# Solid_State_Timer_v1_0.net
KiCad netlist of a schematic drawn in EAGLE
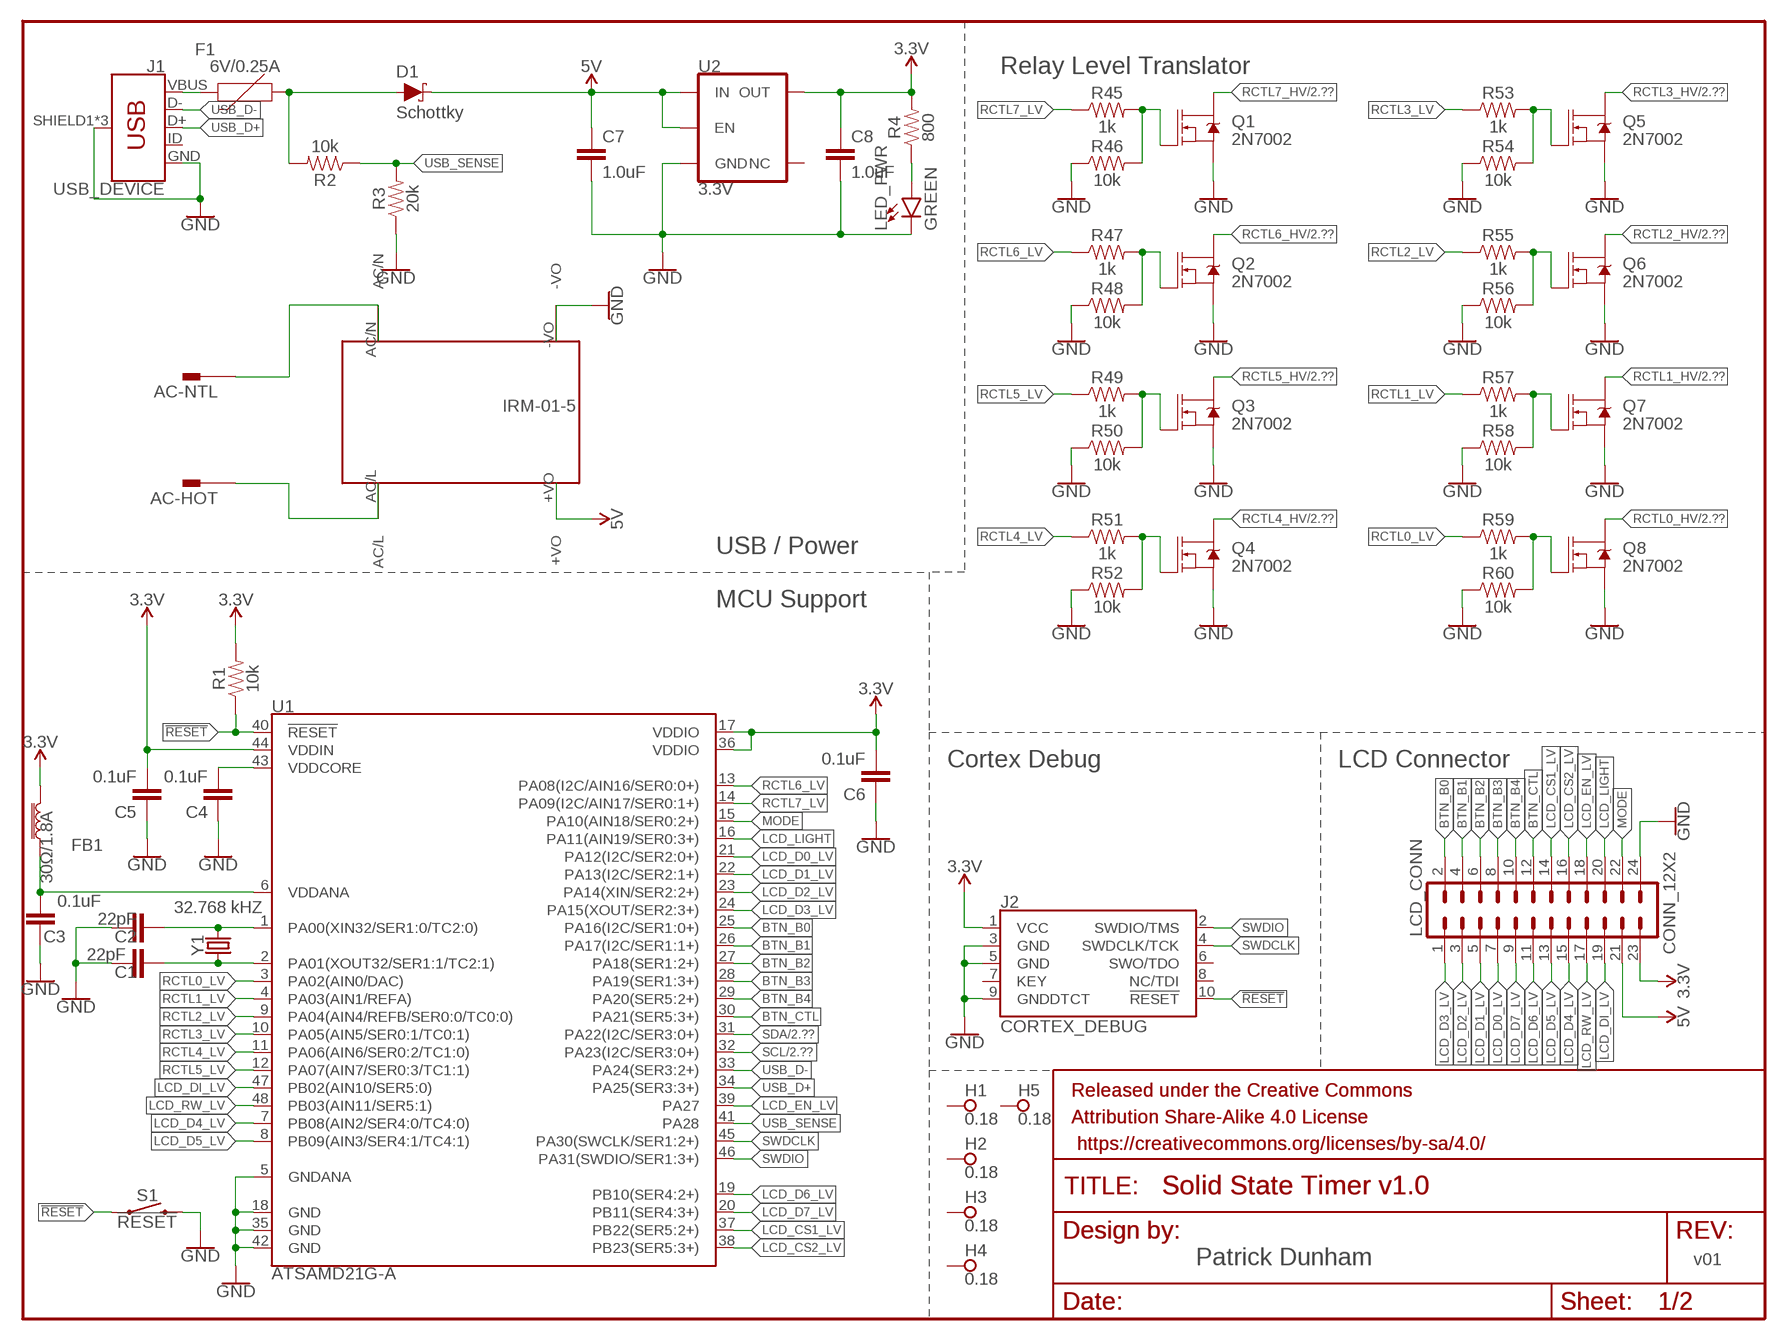
[diagram p0: schematic, sheet 1]
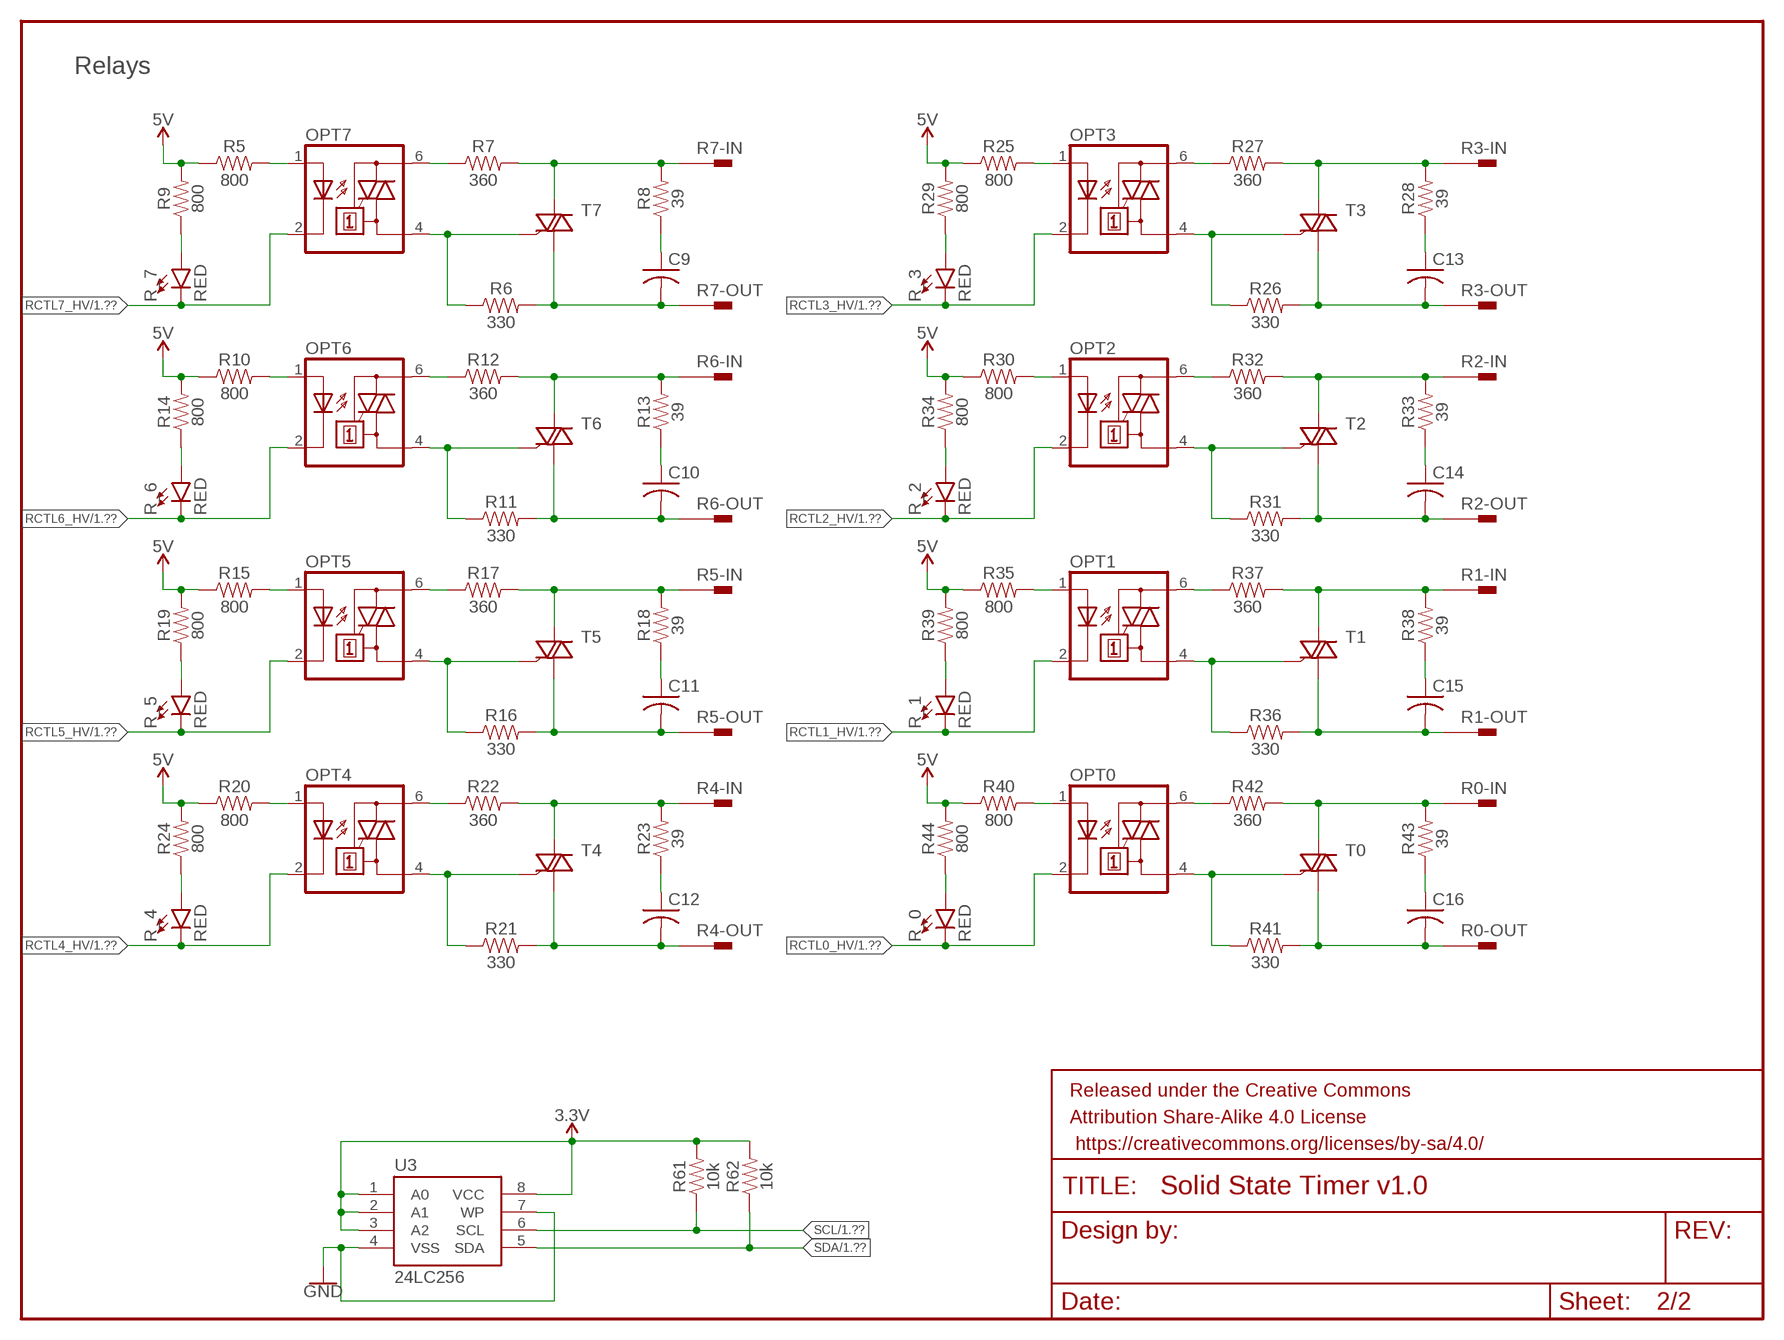
[diagram p1: schematic, sheet 2]

(export (version "E")
  (design (tool "Eeschema 10.0.6"))
  (components
    (comp (ref "C9")
      (value "C-USC1206")
      (footprint "eagle-import:C1206")
      (libsource (lib "eagle-import") (part "C-USC1206"))
    )
    (comp (ref "C10")
      (value "C-USC1206")
      (footprint "eagle-import:C1206")
      (libsource (lib "eagle-import") (part "C-USC1206"))
    )
    (comp (ref "C11")
      (value "C-USC1206")
      (footprint "eagle-import:C1206")
      (libsource (lib "eagle-import") (part "C-USC1206"))
    )
    (comp (ref "C12")
      (value "C-USC1206")
      (footprint "eagle-import:C1206")
      (libsource (lib "eagle-import") (part "C-USC1206"))
    )
    (comp (ref "C13")
      (value "C-USC1206")
      (footprint "eagle-import:C1206")
      (libsource (lib "eagle-import") (part "C-USC1206"))
    )
    (comp (ref "C14")
      (value "C-USC1206")
      (footprint "eagle-import:C1206")
      (libsource (lib "eagle-import") (part "C-USC1206"))
    )
    (comp (ref "C15")
      (value "C-USC1206")
      (footprint "eagle-import:C1206")
      (libsource (lib "eagle-import") (part "C-USC1206"))
    )
    (comp (ref "C16")
      (value "C-USC1206")
      (footprint "eagle-import:C1206")
      (libsource (lib "eagle-import") (part "C-USC1206"))
    )
    (comp (ref "FRAME2")
      (value "FRAME-LETTERNO_PACKAGE")
      (footprint "eagle-import:DUMMY")
      (fields (field (name "DESIGNER") "Nobody"))
      (libsource (lib "eagle-import") (part "FRAME-LETTERNO_PACKAGE"))
    )
    (comp (ref "OPT0")
      (value "MOC3031M")
      (footprint "eagle-import:DIL06")
      (fields (field (name "MF") "FAIRCHILD SEMICONDUCTOR"))
      (libsource (lib "eagle-import") (part "MOC3031M"))
    )
    (comp (ref "OPT1")
      (value "MOC3031M")
      (footprint "eagle-import:DIL06")
      (fields (field (name "MF") "FAIRCHILD SEMICONDUCTOR"))
      (libsource (lib "eagle-import") (part "MOC3031M"))
    )
    (comp (ref "OPT2")
      (value "MOC3031M")
      (footprint "eagle-import:DIL06")
      (fields (field (name "MF") "FAIRCHILD SEMICONDUCTOR"))
      (libsource (lib "eagle-import") (part "MOC3031M"))
    )
    (comp (ref "OPT3")
      (value "MOC3031M")
      (footprint "eagle-import:DIL06")
      (fields (field (name "MF") "FAIRCHILD SEMICONDUCTOR"))
      (libsource (lib "eagle-import") (part "MOC3031M"))
    )
    (comp (ref "OPT4")
      (value "MOC3031M")
      (footprint "eagle-import:DIL06")
      (fields (field (name "MF") "FAIRCHILD SEMICONDUCTOR"))
      (libsource (lib "eagle-import") (part "MOC3031M"))
    )
    (comp (ref "OPT5")
      (value "MOC3031M")
      (footprint "eagle-import:DIL06")
      (fields (field (name "MF") "FAIRCHILD SEMICONDUCTOR"))
      (libsource (lib "eagle-import") (part "MOC3031M"))
    )
    (comp (ref "OPT6")
      (value "MOC3031M")
      (footprint "eagle-import:DIL06")
      (fields (field (name "MF") "FAIRCHILD SEMICONDUCTOR"))
      (libsource (lib "eagle-import") (part "MOC3031M"))
    )
    (comp (ref "OPT7")
      (value "MOC3031M")
      (footprint "eagle-import:DIL06")
      (fields (field (name "MF") "FAIRCHILD SEMICONDUCTOR"))
      (libsource (lib "eagle-import") (part "MOC3031M"))
    )
    (comp (ref "R0-IN")
      (value "PIN262409-1")
      (footprint "eagle-import:62409-1")
      (libsource (lib "eagle-import") (part "PIN262409-1"))
    )
    (comp (ref "R0-OUT")
      (value "PIN262409-1")
      (footprint "eagle-import:62409-1")
      (libsource (lib "eagle-import") (part "PIN262409-1"))
    )
    (comp (ref "R1-IN")
      (value "PIN262409-1")
      (footprint "eagle-import:62409-1")
      (libsource (lib "eagle-import") (part "PIN262409-1"))
    )
    (comp (ref "R1-OUT")
      (value "PIN262409-1")
      (footprint "eagle-import:62409-1")
      (libsource (lib "eagle-import") (part "PIN262409-1"))
    )
    (comp (ref "R2-IN")
      (value "PIN262409-1")
      (footprint "eagle-import:62409-1")
      (libsource (lib "eagle-import") (part "PIN262409-1"))
    )
    (comp (ref "R2-OUT")
      (value "PIN262409-1")
      (footprint "eagle-import:62409-1")
      (libsource (lib "eagle-import") (part "PIN262409-1"))
    )
    (comp (ref "R3-IN")
      (value "PIN262409-1")
      (footprint "eagle-import:62409-1")
      (libsource (lib "eagle-import") (part "PIN262409-1"))
    )
    (comp (ref "R3-OUT")
      (value "PIN262409-1")
      (footprint "eagle-import:62409-1")
      (libsource (lib "eagle-import") (part "PIN262409-1"))
    )
    (comp (ref "R4-IN")
      (value "PIN262409-1")
      (footprint "eagle-import:62409-1")
      (libsource (lib "eagle-import") (part "PIN262409-1"))
    )
    (comp (ref "R4-OUT")
      (value "PIN262409-1")
      (footprint "eagle-import:62409-1")
      (libsource (lib "eagle-import") (part "PIN262409-1"))
    )
    (comp (ref "R5")
      (value "800")
      (footprint "eagle-import:0603")
      (libsource (lib "eagle-import") (part "180OHM-0603-1/10W-1%"))
    )
    (comp (ref "R5-IN")
      (value "PIN262409-1")
      (footprint "eagle-import:62409-1")
      (libsource (lib "eagle-import") (part "PIN262409-1"))
    )
    (comp (ref "R5-OUT")
      (value "PIN262409-1")
      (footprint "eagle-import:62409-1")
      (libsource (lib "eagle-import") (part "PIN262409-1"))
    )
    (comp (ref "R6")
      (value "330")
      (footprint "eagle-import:0603")
      (libsource (lib "eagle-import") (part "330OHM-0603-1/10W-1%"))
    )
    (comp (ref "R6-IN")
      (value "PIN262409-1")
      (footprint "eagle-import:62409-1")
      (libsource (lib "eagle-import") (part "PIN262409-1"))
    )
    (comp (ref "R6-OUT")
      (value "PIN262409-1")
      (footprint "eagle-import:62409-1")
      (libsource (lib "eagle-import") (part "PIN262409-1"))
    )
    (comp (ref "R7")
      (value "360")
      (footprint "eagle-import:0603")
      (libsource (lib "eagle-import") (part "390OHM-0603-1/10W-1%"))
    )
    (comp (ref "R7-IN")
      (value "PIN262409-1")
      (footprint "eagle-import:62409-1")
      (libsource (lib "eagle-import") (part "PIN262409-1"))
    )
    (comp (ref "R7-OUT")
      (value "PIN262409-1")
      (footprint "eagle-import:62409-1")
      (libsource (lib "eagle-import") (part "PIN262409-1"))
    )
    (comp (ref "R8")
      (value "39")
      (footprint "eagle-import:0603")
      (libsource (lib "eagle-import") (part "39KOHM-0603-1/10W-1%"))
    )
    (comp (ref "R9")
      (value "800")
      (footprint "eagle-import:0603")
      (libsource (lib "eagle-import") (part "680OHM-0603-1/10W-5%"))
    )
    (comp (ref "R10")
      (value "800")
      (footprint "eagle-import:0603")
      (libsource (lib "eagle-import") (part "180OHM-0603-1/10W-1%"))
    )
    (comp (ref "R11")
      (value "330")
      (footprint "eagle-import:0603")
      (libsource (lib "eagle-import") (part "330OHM-0603-1/10W-1%"))
    )
    (comp (ref "R12")
      (value "360")
      (footprint "eagle-import:0603")
      (libsource (lib "eagle-import") (part "390OHM-0603-1/10W-1%"))
    )
    (comp (ref "R13")
      (value "39")
      (footprint "eagle-import:0603")
      (libsource (lib "eagle-import") (part "39KOHM-0603-1/10W-1%"))
    )
    (comp (ref "R14")
      (value "800")
      (footprint "eagle-import:0603")
      (libsource (lib "eagle-import") (part "680OHM-0603-1/10W-5%"))
    )
    (comp (ref "R15")
      (value "800")
      (footprint "eagle-import:0603")
      (libsource (lib "eagle-import") (part "180OHM-0603-1/10W-1%"))
    )
    (comp (ref "R16")
      (value "330")
      (footprint "eagle-import:0603")
      (libsource (lib "eagle-import") (part "330OHM-0603-1/10W-1%"))
    )
    (comp (ref "R17")
      (value "360")
      (footprint "eagle-import:0603")
      (libsource (lib "eagle-import") (part "390OHM-0603-1/10W-1%"))
    )
    (comp (ref "R18")
      (value "39")
      (footprint "eagle-import:0603")
      (libsource (lib "eagle-import") (part "39KOHM-0603-1/10W-1%"))
    )
    (comp (ref "R19")
      (value "800")
      (footprint "eagle-import:0603")
      (libsource (lib "eagle-import") (part "680OHM-0603-1/10W-5%"))
    )
    (comp (ref "R20")
      (value "800")
      (footprint "eagle-import:0603")
      (libsource (lib "eagle-import") (part "180OHM-0603-1/10W-1%"))
    )
    (comp (ref "R21")
      (value "330")
      (footprint "eagle-import:0603")
      (libsource (lib "eagle-import") (part "330OHM-0603-1/10W-1%"))
    )
    (comp (ref "R22")
      (value "360")
      (footprint "eagle-import:0603")
      (libsource (lib "eagle-import") (part "390OHM-0603-1/10W-1%"))
    )
    (comp (ref "R23")
      (value "39")
      (footprint "eagle-import:0603")
      (libsource (lib "eagle-import") (part "39KOHM-0603-1/10W-1%"))
    )
    (comp (ref "R24")
      (value "800")
      (footprint "eagle-import:0603")
      (libsource (lib "eagle-import") (part "680OHM-0603-1/10W-5%"))
    )
    (comp (ref "R25")
      (value "800")
      (footprint "eagle-import:0603")
      (libsource (lib "eagle-import") (part "180OHM-0603-1/10W-1%"))
    )
    (comp (ref "R26")
      (value "330")
      (footprint "eagle-import:0603")
      (libsource (lib "eagle-import") (part "330OHM-0603-1/10W-1%"))
    )
    (comp (ref "R27")
      (value "360")
      (footprint "eagle-import:0603")
      (libsource (lib "eagle-import") (part "390OHM-0603-1/10W-1%"))
    )
    (comp (ref "R28")
      (value "39")
      (footprint "eagle-import:0603")
      (libsource (lib "eagle-import") (part "39KOHM-0603-1/10W-1%"))
    )
    (comp (ref "R29")
      (value "800")
      (footprint "eagle-import:0603")
      (libsource (lib "eagle-import") (part "680OHM-0603-1/10W-5%"))
    )
    (comp (ref "R30")
      (value "800")
      (footprint "eagle-import:0603")
      (libsource (lib "eagle-import") (part "180OHM-0603-1/10W-1%"))
    )
    (comp (ref "R31")
      (value "330")
      (footprint "eagle-import:0603")
      (libsource (lib "eagle-import") (part "330OHM-0603-1/10W-1%"))
    )
    (comp (ref "R32")
      (value "360")
      (footprint "eagle-import:0603")
      (libsource (lib "eagle-import") (part "390OHM-0603-1/10W-1%"))
    )
    (comp (ref "R33")
      (value "39")
      (footprint "eagle-import:0603")
      (libsource (lib "eagle-import") (part "39KOHM-0603-1/10W-1%"))
    )
    (comp (ref "R34")
      (value "800")
      (footprint "eagle-import:0603")
      (libsource (lib "eagle-import") (part "680OHM-0603-1/10W-5%"))
    )
    (comp (ref "R35")
      (value "800")
      (footprint "eagle-import:0603")
      (libsource (lib "eagle-import") (part "180OHM-0603-1/10W-1%"))
    )
    (comp (ref "R36")
      (value "330")
      (footprint "eagle-import:0603")
      (libsource (lib "eagle-import") (part "330OHM-0603-1/10W-1%"))
    )
    (comp (ref "R37")
      (value "360")
      (footprint "eagle-import:0603")
      (libsource (lib "eagle-import") (part "390OHM-0603-1/10W-1%"))
    )
    (comp (ref "R38")
      (value "39")
      (footprint "eagle-import:0603")
      (libsource (lib "eagle-import") (part "39KOHM-0603-1/10W-1%"))
    )
    (comp (ref "R39")
      (value "800")
      (footprint "eagle-import:0603")
      (libsource (lib "eagle-import") (part "680OHM-0603-1/10W-5%"))
    )
    (comp (ref "R40")
      (value "800")
      (footprint "eagle-import:0603")
      (libsource (lib "eagle-import") (part "180OHM-0603-1/10W-1%"))
    )
    (comp (ref "R41")
      (value "330")
      (footprint "eagle-import:0603")
      (libsource (lib "eagle-import") (part "330OHM-0603-1/10W-1%"))
    )
    (comp (ref "R42")
      (value "360")
      (footprint "eagle-import:0603")
      (libsource (lib "eagle-import") (part "390OHM-0603-1/10W-1%"))
    )
    (comp (ref "R43")
      (value "39")
      (footprint "eagle-import:0603")
      (libsource (lib "eagle-import") (part "39KOHM-0603-1/10W-1%"))
    )
    (comp (ref "R44")
      (value "800")
      (footprint "eagle-import:0603")
      (libsource (lib "eagle-import") (part "680OHM-0603-1/10W-5%"))
    )
    (comp (ref "R61")
      (value "10k")
      (footprint "eagle-import:0603")
      (libsource (lib "eagle-import") (part "10KOHM-0603-1/10W-1%"))
    )
    (comp (ref "R62")
      (value "10k")
      (footprint "eagle-import:0603")
      (libsource (lib "eagle-import") (part "10KOHM-0603-1/10W-1%"))
    )
    (comp (ref "R_0")
      (value "RED")
      (footprint "eagle-import:LED-0603")
      (libsource (lib "eagle-import") (part "LED-RED0603"))
    )
    (comp (ref "R_1")
      (value "RED")
      (footprint "eagle-import:LED-0603")
      (libsource (lib "eagle-import") (part "LED-RED0603"))
    )
    (comp (ref "R_2")
      (value "RED")
      (footprint "eagle-import:LED-0603")
      (libsource (lib "eagle-import") (part "LED-RED0603"))
    )
    (comp (ref "R_3")
      (value "RED")
      (footprint "eagle-import:LED-0603")
      (libsource (lib "eagle-import") (part "LED-RED0603"))
    )
    (comp (ref "R_4")
      (value "RED")
      (footprint "eagle-import:LED-0603")
      (libsource (lib "eagle-import") (part "LED-RED0603"))
    )
    (comp (ref "R_5")
      (value "RED")
      (footprint "eagle-import:LED-0603")
      (libsource (lib "eagle-import") (part "LED-RED0603"))
    )
    (comp (ref "R_6")
      (value "RED")
      (footprint "eagle-import:LED-0603")
      (libsource (lib "eagle-import") (part "LED-RED0603"))
    )
    (comp (ref "R_7")
      (value "RED")
      (footprint "eagle-import:LED-0603")
      (libsource (lib "eagle-import") (part "LED-RED0603"))
    )
    (comp (ref "T0")
      (value "BT138-V")
      (footprint "eagle-import:TO220BV")
      (libsource (lib "eagle-import") (part "BT138-V"))
    )
    (comp (ref "T1")
      (value "BT138-V")
      (footprint "eagle-import:TO220BV")
      (libsource (lib "eagle-import") (part "BT138-V"))
    )
    (comp (ref "T2")
      (value "BT138-V")
      (footprint "eagle-import:TO220BV")
      (libsource (lib "eagle-import") (part "BT138-V"))
    )
    (comp (ref "T3")
      (value "BT138-V")
      (footprint "eagle-import:TO220BV")
      (libsource (lib "eagle-import") (part "BT138-V"))
    )
    (comp (ref "T4")
      (value "BT138-V")
      (footprint "eagle-import:TO220BV")
      (libsource (lib "eagle-import") (part "BT138-V"))
    )
    (comp (ref "T5")
      (value "BT138-V")
      (footprint "eagle-import:TO220BV")
      (libsource (lib "eagle-import") (part "BT138-V"))
    )
    (comp (ref "T6")
      (value "BT138-V")
      (footprint "eagle-import:TO220BV")
      (libsource (lib "eagle-import") (part "BT138-V"))
    )
    (comp (ref "T7")
      (value "BT138-V")
      (footprint "eagle-import:TO220BV")
      (libsource (lib "eagle-import") (part "BT138-V"))
    )
    (comp (ref "U3")
      (value "24LC256")
      (footprint "eagle-import:SO08")
      (libsource (lib "eagle-import") (part "EEPROM-I2CSMD"))
    )
    (comp (ref "AC-HOT")
      (value "PIN262409-1")
      (footprint "eagle-import:62409-1")
      (libsource (lib "eagle-import") (part "PIN262409-1"))
    )
    (comp (ref "AC-NTL")
      (value "PIN262409-1")
      (footprint "eagle-import:62409-1")
      (libsource (lib "eagle-import") (part "PIN262409-1"))
    )
    (comp (ref "C1")
      (value "22pF")
      (footprint "eagle-import:0603")
      (libsource (lib "eagle-import") (part "22PF-0603-50V-5%"))
    )
    (comp (ref "C2")
      (value "22pF")
      (footprint "eagle-import:0603")
      (libsource (lib "eagle-import") (part "22PF-0603-50V-5%"))
    )
    (comp (ref "C3")
      (value "0.1uF")
      (footprint "eagle-import:0603")
      (libsource (lib "eagle-import") (part "0.1UF-0603-25V-5%"))
    )
    (comp (ref "C4")
      (value "0.1uF")
      (footprint "eagle-import:0603")
      (libsource (lib "eagle-import") (part "0.1UF-0603-25V-5%"))
    )
    (comp (ref "C5")
      (value "0.1uF")
      (footprint "eagle-import:0603")
      (libsource (lib "eagle-import") (part "0.1UF-0603-25V-5%"))
    )
    (comp (ref "C6")
      (value "0.1uF")
      (footprint "eagle-import:0603")
      (libsource (lib "eagle-import") (part "0.1UF-0603-25V-5%"))
    )
    (comp (ref "C7")
      (value "1.0uF")
      (footprint "eagle-import:0603")
      (libsource (lib "eagle-import") (part "1.0UF-0603-16V-10%"))
    )
    (comp (ref "C8")
      (value "1.0uF")
      (footprint "eagle-import:0603")
      (libsource (lib "eagle-import") (part "1.0UF-0603-16V-10%"))
    )
    (comp (ref "D1")
      (value "Schottky")
      (footprint "eagle-import:SOT23-3")
      (libsource (lib "eagle-import") (part "DIODE-SCHOTTKY-ZLLS500"))
    )
    (comp (ref "F1")
      (value "6V/0.25A")
      (footprint "eagle-import:1206")
      (libsource (lib "eagle-import") (part "PPTC_THREE-QUARTER-AMP"))
    )
    (comp (ref "FB1")
      (value "30Ω/1.8A")
      (footprint "eagle-import:0603")
      (libsource (lib "eagle-import") (part "FERRITE_BEAD-0603"))
    )
    (comp (ref "FRAME1")
      (value "FRAME-LETTERNO_PACKAGE")
      (footprint "eagle-import:DUMMY")
      (fields (field (name "DESIGNER") "Nobody"))
      (libsource (lib "eagle-import") (part "FRAME-LETTERNO_PACKAGE"))
    )
    (comp (ref "FRAME3")
      (value "FRAME-LETTERNO_PACKAGE")
      (footprint "eagle-import:DUMMY")
      (fields
        (field (name "DESIGNER") "Nobody")
        (field (name "VERSION") "v01")
        (field (name "DESIGNER_1") "Patrick Dunham")
      )
      (libsource (lib "eagle-import") (part "FRAME-LETTERNO_PACKAGE"))
    )
    (comp (ref "H1")
      (value "0.18")
      (footprint "eagle-import:PAD_0.1800")
      (libsource (lib "eagle-import") (part "SPECIAL_DRILL_0.1800"))
    )
    (comp (ref "H2")
      (value "0.18")
      (footprint "eagle-import:PAD_0.1800")
      (libsource (lib "eagle-import") (part "SPECIAL_DRILL_0.1800"))
    )
    (comp (ref "H3")
      (value "0.18")
      (footprint "eagle-import:PAD_0.1800")
      (libsource (lib "eagle-import") (part "SPECIAL_DRILL_0.1800"))
    )
    (comp (ref "H4")
      (value "0.18")
      (footprint "eagle-import:PAD_0.1800")
      (libsource (lib "eagle-import") (part "SPECIAL_DRILL_0.1800"))
    )
    (comp (ref "H5")
      (value "0.18")
      (footprint "eagle-import:PAD_0.1800")
      (libsource (lib "eagle-import") (part "SPECIAL_DRILL_0.1800"))
    )
    (comp (ref "J1")
      (value "USB_DEVICE")
      (footprint "eagle-import:USB-B-MICRO-SMD")
      (libsource (lib "eagle-import") (part "USB_MICRO-B_FEMALE-SMT"))
    )
    (comp (ref "J2")
      (value "CORTEX_DEBUG")
      (footprint "eagle-import:2X5-PTH-1.27MM")
      (libsource (lib "eagle-import") (part "CORTEX_DEBUG_PTH"))
    )
    (comp (ref "LCD_CONN")
      (value "CONN_12X2")
      (footprint "eagle-import:2X12")
      (libsource (lib "eagle-import") (part "CONN_12X2"))
    )
    (comp (ref "LED_PWR")
      (value "GREEN")
      (footprint "eagle-import:LED-0603")
      (libsource (lib "eagle-import") (part "LED0603"))
    )
    (comp (ref "Q1")
      (value "2N7002")
      (footprint "eagle-import:SOT323")
      (libsource (lib "eagle-import") (part "MOSFET-NCH-2N7002PW"))
    )
    (comp (ref "Q2")
      (value "2N7002")
      (footprint "eagle-import:SOT323")
      (libsource (lib "eagle-import") (part "MOSFET-NCH-2N7002PW"))
    )
    (comp (ref "Q3")
      (value "2N7002")
      (footprint "eagle-import:SOT323")
      (libsource (lib "eagle-import") (part "MOSFET-NCH-2N7002PW"))
    )
    (comp (ref "Q4")
      (value "2N7002")
      (footprint "eagle-import:SOT323")
      (libsource (lib "eagle-import") (part "MOSFET-NCH-2N7002PW"))
    )
    (comp (ref "Q5")
      (value "2N7002")
      (footprint "eagle-import:SOT323")
      (libsource (lib "eagle-import") (part "MOSFET-NCH-2N7002PW"))
    )
    (comp (ref "Q6")
      (value "2N7002")
      (footprint "eagle-import:SOT323")
      (libsource (lib "eagle-import") (part "MOSFET-NCH-2N7002PW"))
    )
    (comp (ref "Q7")
      (value "2N7002")
      (footprint "eagle-import:SOT323")
      (libsource (lib "eagle-import") (part "MOSFET-NCH-2N7002PW"))
    )
    (comp (ref "Q8")
      (value "2N7002")
      (footprint "eagle-import:SOT323")
      (libsource (lib "eagle-import") (part "MOSFET-NCH-2N7002PW"))
    )
    (comp (ref "R1")
      (value "10k")
      (footprint "eagle-import:0603")
      (libsource (lib "eagle-import") (part "10KOHM-0603-1/10W-1%"))
    )
    (comp (ref "R2")
      (value "10k")
      (footprint "eagle-import:0603")
      (libsource (lib "eagle-import") (part "10KOHM-0603-1/10W-1%"))
    )
    (comp (ref "R3")
      (value "20k")
      (footprint "eagle-import:0603")
      (libsource (lib "eagle-import") (part "20KOHM-0603-1/10W-5%"))
    )
    (comp (ref "R4")
      (value "800")
      (footprint "eagle-import:0603")
      (libsource (lib "eagle-import") (part "330OHM-0603-1/10W-1%"))
    )
    (comp (ref "R45")
      (value "1k")
      (footprint "eagle-import:0603")
      (libsource (lib "eagle-import") (part "1KOHM-0603-1/10W-1%"))
    )
    (comp (ref "R46")
      (value "10k")
      (footprint "eagle-import:0603")
      (libsource (lib "eagle-import") (part "10KOHM-0603-1/10W-1%"))
    )
    (comp (ref "R47")
      (value "1k")
      (footprint "eagle-import:0603")
      (libsource (lib "eagle-import") (part "1KOHM-0603-1/10W-1%"))
    )
    (comp (ref "R48")
      (value "10k")
      (footprint "eagle-import:0603")
      (libsource (lib "eagle-import") (part "10KOHM-0603-1/10W-1%"))
    )
    (comp (ref "R49")
      (value "1k")
      (footprint "eagle-import:0603")
      (libsource (lib "eagle-import") (part "1KOHM-0603-1/10W-1%"))
    )
    (comp (ref "R50")
      (value "10k")
      (footprint "eagle-import:0603")
      (libsource (lib "eagle-import") (part "10KOHM-0603-1/10W-1%"))
    )
    (comp (ref "R51")
      (value "1k")
      (footprint "eagle-import:0603")
      (libsource (lib "eagle-import") (part "1KOHM-0603-1/10W-1%"))
    )
    (comp (ref "R52")
      (value "10k")
      (footprint "eagle-import:0603")
      (libsource (lib "eagle-import") (part "10KOHM-0603-1/10W-1%"))
    )
    (comp (ref "R53")
      (value "1k")
      (footprint "eagle-import:0603")
      (libsource (lib "eagle-import") (part "1KOHM-0603-1/10W-1%"))
    )
    (comp (ref "R54")
      (value "10k")
      (footprint "eagle-import:0603")
      (libsource (lib "eagle-import") (part "10KOHM-0603-1/10W-1%"))
    )
    (comp (ref "R55")
      (value "1k")
      (footprint "eagle-import:0603")
      (libsource (lib "eagle-import") (part "1KOHM-0603-1/10W-1%"))
    )
    (comp (ref "R56")
      (value "10k")
      (footprint "eagle-import:0603")
      (libsource (lib "eagle-import") (part "10KOHM-0603-1/10W-1%"))
    )
    (comp (ref "R57")
      (value "1k")
      (footprint "eagle-import:0603")
      (libsource (lib "eagle-import") (part "1KOHM-0603-1/10W-1%"))
    )
    (comp (ref "R58")
      (value "10k")
      (footprint "eagle-import:0603")
      (libsource (lib "eagle-import") (part "10KOHM-0603-1/10W-1%"))
    )
    (comp (ref "R59")
      (value "1k")
      (footprint "eagle-import:0603")
      (libsource (lib "eagle-import") (part "1KOHM-0603-1/10W-1%"))
    )
    (comp (ref "R60")
      (value "10k")
      (footprint "eagle-import:0603")
      (libsource (lib "eagle-import") (part "10KOHM-0603-1/10W-1%"))
    )
    (comp (ref "S1")
      (value "!RESET")
      (footprint "eagle-import:TACTILE_SWITCH_PTH_RIGHT_ANGLE_KIT")
      (libsource (lib "eagle-import") (part "MOMENTARY-SWITCH-SPST-PTH-RIGHT-ANGLE-KIT"))
    )
    (comp (ref "U$1")
      (value "IRM-05-1")
      (footprint "eagle-import:IRM-01-5")
      (libsource (lib "eagle-import") (part "IRM-05-1"))
    )
    (comp (ref "U1")
      (value "ATSAMD21G-A")
      (footprint "eagle-import:TQFP-48")
      (libsource (lib "eagle-import") (part "ATSAMD21G-A"))
    )
    (comp (ref "U2")
      (value "3.3V")
      (footprint "eagle-import:SOT23-5")
      (libsource (lib "eagle-import") (part "V_REG_AP2112K-3.3V"))
    )
    (comp (ref "Y1")
      (value "32.768 kHZ")
      (footprint "eagle-import:CRYSTAL-SMD-3.2X1.5MM")
      (libsource (lib "eagle-import") (part "CRYSTALSMD-3.2X1.5"))
    )
  )
  (nets
    (net (code "1") (name "3.3V") (class "Default")
      (node (ref "C5") (pin "2") (pinfunction "2_2") (pintype "passive"))
      (node (ref "C6") (pin "2") (pinfunction "2_2") (pintype "passive"))
      (node (ref "C8") (pin "1") (pinfunction "1_1") (pintype "passive"))
      (node (ref "FB1") (pin "2") (pinfunction "2_2") (pintype "passive"))
      (node (ref "J2") (pin "1") (pinfunction "VCC_1") (pintype "bidirectional"))
      (node (ref "LCD_CONN") (pin "23") (pinfunction "23_23") (pintype "passive"))
      (node (ref "R1") (pin "2") (pinfunction "2_2") (pintype "passive"))
      (node (ref "R4") (pin "2") (pinfunction "2_2") (pintype "passive"))
      (node (ref "R61") (pin "2") (pinfunction "2_2") (pintype "passive"))
      (node (ref "R62") (pin "2") (pinfunction "2_2") (pintype "passive"))
      (node (ref "U1") (pin "17") (pinfunction "VDDIO_17") (pintype "bidirectional"))
      (node (ref "U1") (pin "36") (pinfunction "VDDIO_36") (pintype "bidirectional"))
      (node (ref "U1") (pin "44") (pinfunction "VDDIN_44") (pintype "bidirectional"))
      (node (ref "U2") (pin "5") (pinfunction "OUT_5") (pintype "passive"))
      (node (ref "U3") (pin "1") (pinfunction "A0_1") (pintype "bidirectional"))
      (node (ref "U3") (pin "2") (pinfunction "A1_2") (pintype "bidirectional"))
      (node (ref "U3") (pin "3") (pinfunction "A2_3") (pintype "bidirectional"))
      (node (ref "U3") (pin "8") (pinfunction "VCC_8") (pintype "power_in"))
    )
    (net (code "2") (name "5V") (class "Default")
      (node (ref "C7") (pin "1") (pinfunction "1_1") (pintype "passive"))
      (node (ref "D1") (pin "3") (pinfunction "C_3") (pintype "passive"))
      (node (ref "LCD_CONN") (pin "21") (pinfunction "21_21") (pintype "passive"))
      (node (ref "R10") (pin "1") (pinfunction "1_1") (pintype "passive"))
      (node (ref "R14") (pin "2") (pinfunction "2_2") (pintype "passive"))
      (node (ref "R15") (pin "1") (pinfunction "1_1") (pintype "passive"))
      (node (ref "R19") (pin "2") (pinfunction "2_2") (pintype "passive"))
      (node (ref "R20") (pin "1") (pinfunction "1_1") (pintype "passive"))
      (node (ref "R24") (pin "2") (pinfunction "2_2") (pintype "passive"))
      (node (ref "R25") (pin "1") (pinfunction "1_1") (pintype "passive"))
      (node (ref "R29") (pin "2") (pinfunction "2_2") (pintype "passive"))
      (node (ref "R30") (pin "1") (pinfunction "1_1") (pintype "passive"))
      (node (ref "R34") (pin "2") (pinfunction "2_2") (pintype "passive"))
      (node (ref "R35") (pin "1") (pinfunction "1_1") (pintype "passive"))
      (node (ref "R39") (pin "2") (pinfunction "2_2") (pintype "passive"))
      (node (ref "R40") (pin "1") (pinfunction "1_1") (pintype "passive"))
      (node (ref "R44") (pin "2") (pinfunction "2_2") (pintype "passive"))
      (node (ref "R5") (pin "1") (pinfunction "1_1") (pintype "passive"))
      (node (ref "R9") (pin "2") (pinfunction "2_2") (pintype "passive"))
      (node (ref "U$1") (pin "+VO") (pinfunction "+VO_+VO") (pintype "bidirectional"))
      (node (ref "U2") (pin "1") (pinfunction "IN_1") (pintype "input"))
      (node (ref "U2") (pin "3") (pinfunction "EN_3") (pintype "input"))
    )
    (net (code "3") (name "BTN_B0") (class "Default")
      (node (ref "LCD_CONN") (pin "2") (pinfunction "2_2") (pintype "passive"))
      (node (ref "U1") (pin "25") (pinfunction "PA16(I2C/SER1:0+)_25") (pintype "bidirectional"))
    )
    (net (code "4") (name "BTN_B1") (class "Default")
      (node (ref "LCD_CONN") (pin "4") (pinfunction "4_4") (pintype "passive"))
      (node (ref "U1") (pin "26") (pinfunction "PA17(I2C/SER1:1+)_26") (pintype "bidirectional"))
    )
    (net (code "5") (name "BTN_B2") (class "Default")
      (node (ref "LCD_CONN") (pin "6") (pinfunction "6_6") (pintype "passive"))
      (node (ref "U1") (pin "27") (pinfunction "PA18(SER1:2+)_27") (pintype "bidirectional"))
    )
    (net (code "6") (name "BTN_B3") (class "Default")
      (node (ref "LCD_CONN") (pin "8") (pinfunction "8_8") (pintype "passive"))
      (node (ref "U1") (pin "28") (pinfunction "PA19(SER1:3+)_28") (pintype "bidirectional"))
    )
    (net (code "7") (name "BTN_B4") (class "Default")
      (node (ref "LCD_CONN") (pin "10") (pinfunction "10_10") (pintype "passive"))
      (node (ref "U1") (pin "29") (pinfunction "PA20(SER5:2+)_29") (pintype "bidirectional"))
    )
    (net (code "8") (name "BTN_CTL") (class "Default")
      (node (ref "LCD_CONN") (pin "12") (pinfunction "12_12") (pintype "passive"))
      (node (ref "U1") (pin "30") (pinfunction "PA21(SER5:3+)_30") (pintype "bidirectional"))
    )
    (net (code "9") (name "GND") (class "Default")
      (node (ref "C1") (pin "1") (pinfunction "1_1") (pintype "passive"))
      (node (ref "C2") (pin "1") (pinfunction "1_1") (pintype "passive"))
      (node (ref "C3") (pin "1") (pinfunction "1_1") (pintype "passive"))
      (node (ref "C4") (pin "1") (pinfunction "1_1") (pintype "passive"))
      (node (ref "C5") (pin "1") (pinfunction "1_1") (pintype "passive"))
      (node (ref "C6") (pin "1") (pinfunction "1_1") (pintype "passive"))
      (node (ref "C7") (pin "2") (pinfunction "2_2") (pintype "passive"))
      (node (ref "C8") (pin "2") (pinfunction "2_2") (pintype "passive"))
      (node (ref "J1") (pin "GND") (pinfunction "GND_GND") (pintype "power_in"))
      (node (ref "J1") (pin "SHIELD1") (pinfunction "SHIELD_SHIELD1") (pintype "bidirectional"))
      (node (ref "J1") (pin "SHIELD2") (pinfunction "SHIELD_SHIELD2") (pintype "bidirectional"))
      (node (ref "J1") (pin "SHIELD3") (pinfunction "SHIELD_SHIELD3") (pintype "bidirectional"))
      (node (ref "J2") (pin "3") (pinfunction "GND_3") (pintype "bidirectional"))
      (node (ref "J2") (pin "5") (pinfunction "GND_5") (pintype "bidirectional"))
      (node (ref "J2") (pin "9") (pinfunction "GNDDTCT_9") (pintype "bidirectional"))
      (node (ref "LCD_CONN") (pin "24") (pinfunction "24_24") (pintype "passive"))
      (node (ref "LED_PWR") (pin "C") (pinfunction "C_C") (pintype "passive"))
      (node (ref "Q1") (pin "2") (pinfunction "S_2") (pintype "bidirectional"))
      (node (ref "Q2") (pin "2") (pinfunction "S_2") (pintype "bidirectional"))
      (node (ref "Q3") (pin "2") (pinfunction "S_2") (pintype "bidirectional"))
      (node (ref "Q4") (pin "2") (pinfunction "S_2") (pintype "bidirectional"))
      (node (ref "Q5") (pin "2") (pinfunction "S_2") (pintype "bidirectional"))
      (node (ref "Q6") (pin "2") (pinfunction "S_2") (pintype "bidirectional"))
      (node (ref "Q7") (pin "2") (pinfunction "S_2") (pintype "bidirectional"))
      (node (ref "Q8") (pin "2") (pinfunction "S_2") (pintype "bidirectional"))
      (node (ref "R3") (pin "1") (pinfunction "1_1") (pintype "passive"))
      (node (ref "R46") (pin "1") (pinfunction "1_1") (pintype "passive"))
      (node (ref "R48") (pin "1") (pinfunction "1_1") (pintype "passive"))
      (node (ref "R50") (pin "1") (pinfunction "1_1") (pintype "passive"))
      (node (ref "R52") (pin "1") (pinfunction "1_1") (pintype "passive"))
      (node (ref "R54") (pin "1") (pinfunction "1_1") (pintype "passive"))
      (node (ref "R56") (pin "1") (pinfunction "1_1") (pintype "passive"))
      (node (ref "R58") (pin "1") (pinfunction "1_1") (pintype "passive"))
      (node (ref "R60") (pin "1") (pinfunction "1_1") (pintype "passive"))
      (node (ref "S1") (pin "2") (pinfunction "2_2") (pintype "passive"))
      (node (ref "U$1") (pin "-VO") (pinfunction "-VO_-VO") (pintype "bidirectional"))
      (node (ref "U1") (pin "18") (pinfunction "GND_18") (pintype "bidirectional"))
      (node (ref "U1") (pin "35") (pinfunction "GND_35") (pintype "bidirectional"))
      (node (ref "U1") (pin "42") (pinfunction "GND_42") (pintype "bidirectional"))
      (node (ref "U1") (pin "5") (pinfunction "GNDANA_5") (pintype "bidirectional"))
      (node (ref "U2") (pin "2") (pinfunction "GND_2") (pintype "input"))
      (node (ref "U3") (pin "4") (pinfunction "VSS_4") (pintype "power_in"))
      (node (ref "U3") (pin "7") (pinfunction "WP_7") (pintype "bidirectional"))
    )
    (net (code "10") (name "LCD_CS1_LV") (class "Default")
      (node (ref "LCD_CONN") (pin "14") (pinfunction "14_14") (pintype "passive"))
      (node (ref "U1") (pin "37") (pinfunction "PB22(SER5:2+)_37") (pintype "bidirectional"))
    )
    (net (code "11") (name "LCD_CS2_LV") (class "Default")
      (node (ref "LCD_CONN") (pin "16") (pinfunction "16_16") (pintype "passive"))
      (node (ref "U1") (pin "38") (pinfunction "PB23(SER5:3+)_38") (pintype "bidirectional"))
    )
    (net (code "12") (name "LCD_D0_LV") (class "Default")
      (node (ref "LCD_CONN") (pin "7") (pinfunction "7_7") (pintype "passive"))
      (node (ref "U1") (pin "21") (pinfunction "PA12(I2C/SER2:0+)_21") (pintype "bidirectional"))
    )
    (net (code "13") (name "LCD_D1_LV") (class "Default")
      (node (ref "LCD_CONN") (pin "5") (pinfunction "5_5") (pintype "passive"))
      (node (ref "U1") (pin "22") (pinfunction "PA13(I2C/SER2:1+)_22") (pintype "bidirectional"))
    )
    (net (code "14") (name "LCD_D2_LV") (class "Default")
      (node (ref "LCD_CONN") (pin "3") (pinfunction "3_3") (pintype "passive"))
      (node (ref "U1") (pin "23") (pinfunction "PA14(XIN/SER2:2+)_23") (pintype "bidirectional"))
    )
    (net (code "15") (name "LCD_D3_LV") (class "Default")
      (node (ref "LCD_CONN") (pin "1") (pinfunction "1_1") (pintype "passive"))
      (node (ref "U1") (pin "24") (pinfunction "PA15(XOUT/SER2:3+)_24") (pintype "bidirectional"))
    )
    (net (code "16") (name "LCD_D4_LV") (class "Default")
      (node (ref "LCD_CONN") (pin "15") (pinfunction "15_15") (pintype "passive"))
      (node (ref "U1") (pin "7") (pinfunction "PB08(AIN2/SER4:0/TC4:0)_7") (pintype "bidirectional"))
    )
    (net (code "17") (name "LCD_D5_LV") (class "Default")
      (node (ref "LCD_CONN") (pin "13") (pinfunction "13_13") (pintype "passive"))
      (node (ref "U1") (pin "8") (pinfunction "PB09(AIN3/SER4:1/TC4:1)_8") (pintype "bidirectional"))
    )
    (net (code "18") (name "LCD_D6_LV") (class "Default")
      (node (ref "LCD_CONN") (pin "11") (pinfunction "11_11") (pintype "passive"))
      (node (ref "U1") (pin "19") (pinfunction "PB10(SER4:2+)_19") (pintype "bidirectional"))
    )
    (net (code "19") (name "LCD_D7_LV") (class "Default")
      (node (ref "LCD_CONN") (pin "9") (pinfunction "9_9") (pintype "passive"))
      (node (ref "U1") (pin "20") (pinfunction "PB11(SER4:3+)_20") (pintype "bidirectional"))
    )
    (net (code "20") (name "LCD_DI_LV") (class "Default")
      (node (ref "LCD_CONN") (pin "19") (pinfunction "19_19") (pintype "passive"))
      (node (ref "U1") (pin "47") (pinfunction "PB02(AIN10/SER5:0)_47") (pintype "bidirectional"))
    )
    (net (code "21") (name "LCD_EN_LV") (class "Default")
      (node (ref "LCD_CONN") (pin "18") (pinfunction "18_18") (pintype "passive"))
      (node (ref "U1") (pin "39") (pinfunction "PA27_39") (pintype "bidirectional"))
    )
    (net (code "22") (name "LCD_LIGHT") (class "Default")
      (node (ref "LCD_CONN") (pin "20") (pinfunction "20_20") (pintype "passive"))
      (node (ref "U1") (pin "16") (pinfunction "PA11(AIN19/SER0:3+)_16") (pintype "bidirectional"))
    )
    (net (code "23") (name "LCD_RW_LV") (class "Default")
      (node (ref "LCD_CONN") (pin "17") (pinfunction "17_17") (pintype "passive"))
      (node (ref "U1") (pin "48") (pinfunction "PB03(AIN11/SER5:1)_48") (pintype "bidirectional"))
    )
    (net (code "24") (name "MODE") (class "Default")
      (node (ref "LCD_CONN") (pin "22") (pinfunction "22_22") (pintype "passive"))
      (node (ref "U1") (pin "15") (pinfunction "PA10(AIN18/SER0:2+)_15") (pintype "bidirectional"))
    )
    (net (code "25") (name "Net-(AC-HOT-1-PadA1)") (class "Default")
      (node (ref "AC-HOT") (pin "A1") (pinfunction "1_A1") (pintype "passive"))
      (node (ref "AC-HOT") (pin "A2") (pinfunction "1_A2") (pintype "passive"))
      (node (ref "U$1") (pin "AC/L") (pinfunction "AC/L_AC/L") (pintype "bidirectional"))
    )
    (net (code "26") (name "Net-(AC-NTL-1-PadA1)") (class "Default")
      (node (ref "AC-NTL") (pin "A1") (pinfunction "1_A1") (pintype "passive"))
      (node (ref "AC-NTL") (pin "A2") (pinfunction "1_A2") (pintype "passive"))
      (node (ref "U$1") (pin "AC/N") (pinfunction "AC/N_AC/N") (pintype "bidirectional"))
    )
    (net (code "27") (name "Net-(C9-Pad1)") (class "Default")
      (node (ref "C9") (pin "1") (pinfunction "1_1") (pintype "passive"))
      (node (ref "R8") (pin "1") (pinfunction "1_1") (pintype "passive"))
    )
    (net (code "28") (name "Net-(C10-Pad1)") (class "Default")
      (node (ref "C10") (pin "1") (pinfunction "1_1") (pintype "passive"))
      (node (ref "R13") (pin "1") (pinfunction "1_1") (pintype "passive"))
    )
    (net (code "29") (name "Net-(C11-Pad1)") (class "Default")
      (node (ref "C11") (pin "1") (pinfunction "1_1") (pintype "passive"))
      (node (ref "R18") (pin "1") (pinfunction "1_1") (pintype "passive"))
    )
    (net (code "30") (name "Net-(C12-Pad1)") (class "Default")
      (node (ref "C12") (pin "1") (pinfunction "1_1") (pintype "passive"))
      (node (ref "R23") (pin "1") (pinfunction "1_1") (pintype "passive"))
    )
    (net (code "31") (name "Net-(C13-Pad1)") (class "Default")
      (node (ref "C13") (pin "1") (pinfunction "1_1") (pintype "passive"))
      (node (ref "R28") (pin "1") (pinfunction "1_1") (pintype "passive"))
    )
    (net (code "32") (name "Net-(C14-Pad1)") (class "Default")
      (node (ref "C14") (pin "1") (pinfunction "1_1") (pintype "passive"))
      (node (ref "R33") (pin "1") (pinfunction "1_1") (pintype "passive"))
    )
    (net (code "33") (name "Net-(C15-Pad1)") (class "Default")
      (node (ref "C15") (pin "1") (pinfunction "1_1") (pintype "passive"))
      (node (ref "R38") (pin "1") (pinfunction "1_1") (pintype "passive"))
    )
    (net (code "34") (name "Net-(C16-Pad1)") (class "Default")
      (node (ref "C16") (pin "1") (pinfunction "1_1") (pintype "passive"))
      (node (ref "R43") (pin "1") (pinfunction "1_1") (pintype "passive"))
    )
    (net (code "35") (name "Net-(D1-A)") (class "Default")
      (node (ref "D1") (pin "1") (pinfunction "A_1") (pintype "passive"))
      (node (ref "F1") (pin "1") (pinfunction "1_1") (pintype "bidirectional"))
      (node (ref "R2") (pin "2") (pinfunction "2_2") (pintype "passive"))
    )
    (net (code "36") (name "Net-(F1-Pad2)") (class "Default")
      (node (ref "F1") (pin "2") (pinfunction "2_2") (pintype "bidirectional"))
      (node (ref "J1") (pin "VBUS") (pinfunction "VBUS_VBUS") (pintype "power_in"))
    )
    (net (code "37") (name "Net-(LED_PWR-PadA)") (class "Default")
      (node (ref "LED_PWR") (pin "A") (pinfunction "A_A") (pintype "passive"))
      (node (ref "R4") (pin "1") (pinfunction "1_1") (pintype "passive"))
    )
    (net (code "38") (name "Net-(OPT0-A)") (class "Default")
      (node (ref "OPT0") (pin "1") (pinfunction "A_1") (pintype "passive"))
      (node (ref "R40") (pin "2") (pinfunction "2_2") (pintype "passive"))
    )
    (net (code "39") (name "Net-(OPT0-A1)") (class "Default")
      (node (ref "OPT0") (pin "4") (pinfunction "A1_4") (pintype "passive"))
      (node (ref "R41") (pin "1") (pinfunction "1_1") (pintype "passive"))
      (node (ref "T0") (pin "G") (pinfunction "G_G") (pintype "passive"))
    )
    (net (code "40") (name "Net-(OPT0-A2)") (class "Default")
      (node (ref "OPT0") (pin "6") (pinfunction "A2_6") (pintype "passive"))
      (node (ref "R42") (pin "1") (pinfunction "1_1") (pintype "passive"))
    )
    (net (code "41") (name "Net-(OPT1-A)") (class "Default")
      (node (ref "OPT1") (pin "1") (pinfunction "A_1") (pintype "passive"))
      (node (ref "R35") (pin "2") (pinfunction "2_2") (pintype "passive"))
    )
    (net (code "42") (name "Net-(OPT1-A1)") (class "Default")
      (node (ref "OPT1") (pin "4") (pinfunction "A1_4") (pintype "passive"))
      (node (ref "R36") (pin "1") (pinfunction "1_1") (pintype "passive"))
      (node (ref "T1") (pin "G") (pinfunction "G_G") (pintype "passive"))
    )
    (net (code "43") (name "Net-(OPT1-A2)") (class "Default")
      (node (ref "OPT1") (pin "6") (pinfunction "A2_6") (pintype "passive"))
      (node (ref "R37") (pin "1") (pinfunction "1_1") (pintype "passive"))
    )
    (net (code "44") (name "Net-(OPT2-A)") (class "Default")
      (node (ref "OPT2") (pin "1") (pinfunction "A_1") (pintype "passive"))
      (node (ref "R30") (pin "2") (pinfunction "2_2") (pintype "passive"))
    )
    (net (code "45") (name "Net-(OPT2-A1)") (class "Default")
      (node (ref "OPT2") (pin "4") (pinfunction "A1_4") (pintype "passive"))
      (node (ref "R31") (pin "1") (pinfunction "1_1") (pintype "passive"))
      (node (ref "T2") (pin "G") (pinfunction "G_G") (pintype "passive"))
    )
    (net (code "46") (name "Net-(OPT2-A2)") (class "Default")
      (node (ref "OPT2") (pin "6") (pinfunction "A2_6") (pintype "passive"))
      (node (ref "R32") (pin "1") (pinfunction "1_1") (pintype "passive"))
    )
    (net (code "47") (name "Net-(OPT3-A)") (class "Default")
      (node (ref "OPT3") (pin "1") (pinfunction "A_1") (pintype "passive"))
      (node (ref "R25") (pin "2") (pinfunction "2_2") (pintype "passive"))
    )
    (net (code "48") (name "Net-(OPT3-A1)") (class "Default")
      (node (ref "OPT3") (pin "4") (pinfunction "A1_4") (pintype "passive"))
      (node (ref "R26") (pin "1") (pinfunction "1_1") (pintype "passive"))
      (node (ref "T3") (pin "G") (pinfunction "G_G") (pintype "passive"))
    )
    (net (code "49") (name "Net-(OPT3-A2)") (class "Default")
      (node (ref "OPT3") (pin "6") (pinfunction "A2_6") (pintype "passive"))
      (node (ref "R27") (pin "1") (pinfunction "1_1") (pintype "passive"))
    )
    (net (code "50") (name "Net-(OPT4-A)") (class "Default")
      (node (ref "OPT4") (pin "1") (pinfunction "A_1") (pintype "passive"))
      (node (ref "R20") (pin "2") (pinfunction "2_2") (pintype "passive"))
    )
    (net (code "51") (name "Net-(OPT4-A1)") (class "Default")
      (node (ref "OPT4") (pin "4") (pinfunction "A1_4") (pintype "passive"))
      (node (ref "R21") (pin "1") (pinfunction "1_1") (pintype "passive"))
      (node (ref "T4") (pin "G") (pinfunction "G_G") (pintype "passive"))
    )
    (net (code "52") (name "Net-(OPT4-A2)") (class "Default")
      (node (ref "OPT4") (pin "6") (pinfunction "A2_6") (pintype "passive"))
      (node (ref "R22") (pin "1") (pinfunction "1_1") (pintype "passive"))
    )
    (net (code "53") (name "Net-(OPT5-A)") (class "Default")
      (node (ref "OPT5") (pin "1") (pinfunction "A_1") (pintype "passive"))
      (node (ref "R15") (pin "2") (pinfunction "2_2") (pintype "passive"))
    )
    (net (code "54") (name "Net-(OPT5-A1)") (class "Default")
      (node (ref "OPT5") (pin "4") (pinfunction "A1_4") (pintype "passive"))
      (node (ref "R16") (pin "1") (pinfunction "1_1") (pintype "passive"))
      (node (ref "T5") (pin "G") (pinfunction "G_G") (pintype "passive"))
    )
    (net (code "55") (name "Net-(OPT5-A2)") (class "Default")
      (node (ref "OPT5") (pin "6") (pinfunction "A2_6") (pintype "passive"))
      (node (ref "R17") (pin "1") (pinfunction "1_1") (pintype "passive"))
    )
    (net (code "56") (name "Net-(OPT6-A)") (class "Default")
      (node (ref "OPT6") (pin "1") (pinfunction "A_1") (pintype "passive"))
      (node (ref "R10") (pin "2") (pinfunction "2_2") (pintype "passive"))
    )
    (net (code "57") (name "Net-(OPT6-A1)") (class "Default")
      (node (ref "OPT6") (pin "4") (pinfunction "A1_4") (pintype "passive"))
      (node (ref "R11") (pin "1") (pinfunction "1_1") (pintype "passive"))
      (node (ref "T6") (pin "G") (pinfunction "G_G") (pintype "passive"))
    )
    (net (code "58") (name "Net-(OPT6-A2)") (class "Default")
      (node (ref "OPT6") (pin "6") (pinfunction "A2_6") (pintype "passive"))
      (node (ref "R12") (pin "1") (pinfunction "1_1") (pintype "passive"))
    )
    (net (code "59") (name "Net-(OPT7-A)") (class "Default")
      (node (ref "OPT7") (pin "1") (pinfunction "A_1") (pintype "passive"))
      (node (ref "R5") (pin "2") (pinfunction "2_2") (pintype "passive"))
    )
    (net (code "60") (name "Net-(OPT7-A1)") (class "Default")
      (node (ref "OPT7") (pin "4") (pinfunction "A1_4") (pintype "passive"))
      (node (ref "R6") (pin "1") (pinfunction "1_1") (pintype "passive"))
      (node (ref "T7") (pin "G") (pinfunction "G_G") (pintype "passive"))
    )
    (net (code "61") (name "Net-(OPT7-A2)") (class "Default")
      (node (ref "OPT7") (pin "6") (pinfunction "A2_6") (pintype "passive"))
      (node (ref "R7") (pin "1") (pinfunction "1_1") (pintype "passive"))
    )
    (net (code "62") (name "Net-(Q1-G)") (class "Default")
      (node (ref "Q1") (pin "1") (pinfunction "G_1") (pintype "bidirectional"))
      (node (ref "R45") (pin "2") (pinfunction "2_2") (pintype "passive"))
      (node (ref "R46") (pin "2") (pinfunction "2_2") (pintype "passive"))
    )
    (net (code "63") (name "Net-(Q2-G)") (class "Default")
      (node (ref "Q2") (pin "1") (pinfunction "G_1") (pintype "bidirectional"))
      (node (ref "R47") (pin "2") (pinfunction "2_2") (pintype "passive"))
      (node (ref "R48") (pin "2") (pinfunction "2_2") (pintype "passive"))
    )
    (net (code "64") (name "Net-(Q3-G)") (class "Default")
      (node (ref "Q3") (pin "1") (pinfunction "G_1") (pintype "bidirectional"))
      (node (ref "R49") (pin "2") (pinfunction "2_2") (pintype "passive"))
      (node (ref "R50") (pin "2") (pinfunction "2_2") (pintype "passive"))
    )
    (net (code "65") (name "Net-(Q4-G)") (class "Default")
      (node (ref "Q4") (pin "1") (pinfunction "G_1") (pintype "bidirectional"))
      (node (ref "R51") (pin "2") (pinfunction "2_2") (pintype "passive"))
      (node (ref "R52") (pin "2") (pinfunction "2_2") (pintype "passive"))
    )
    (net (code "66") (name "Net-(Q5-G)") (class "Default")
      (node (ref "Q5") (pin "1") (pinfunction "G_1") (pintype "bidirectional"))
      (node (ref "R53") (pin "2") (pinfunction "2_2") (pintype "passive"))
      (node (ref "R54") (pin "2") (pinfunction "2_2") (pintype "passive"))
    )
    (net (code "67") (name "Net-(Q6-G)") (class "Default")
      (node (ref "Q6") (pin "1") (pinfunction "G_1") (pintype "bidirectional"))
      (node (ref "R55") (pin "2") (pinfunction "2_2") (pintype "passive"))
      (node (ref "R56") (pin "2") (pinfunction "2_2") (pintype "passive"))
    )
    (net (code "68") (name "Net-(Q7-G)") (class "Default")
      (node (ref "Q7") (pin "1") (pinfunction "G_1") (pintype "bidirectional"))
      (node (ref "R57") (pin "2") (pinfunction "2_2") (pintype "passive"))
      (node (ref "R58") (pin "2") (pinfunction "2_2") (pintype "passive"))
    )
    (net (code "69") (name "Net-(Q8-G)") (class "Default")
      (node (ref "Q8") (pin "1") (pinfunction "G_1") (pintype "bidirectional"))
      (node (ref "R59") (pin "2") (pinfunction "2_2") (pintype "passive"))
      (node (ref "R60") (pin "2") (pinfunction "2_2") (pintype "passive"))
    )
    (net (code "70") (name "Net-(R9-Pad1)") (class "Default")
      (node (ref "R9") (pin "1") (pinfunction "1_1") (pintype "passive"))
      (node (ref "R_7") (pin "A") (pinfunction "A_A") (pintype "passive"))
    )
    (net (code "71") (name "Net-(R14-Pad1)") (class "Default")
      (node (ref "R14") (pin "1") (pinfunction "1_1") (pintype "passive"))
      (node (ref "R_6") (pin "A") (pinfunction "A_A") (pintype "passive"))
    )
    (net (code "72") (name "Net-(R19-Pad1)") (class "Default")
      (node (ref "R19") (pin "1") (pinfunction "1_1") (pintype "passive"))
      (node (ref "R_5") (pin "A") (pinfunction "A_A") (pintype "passive"))
    )
    (net (code "73") (name "Net-(R24-Pad1)") (class "Default")
      (node (ref "R24") (pin "1") (pinfunction "1_1") (pintype "passive"))
      (node (ref "R_4") (pin "A") (pinfunction "A_A") (pintype "passive"))
    )
    (net (code "74") (name "Net-(R29-Pad1)") (class "Default")
      (node (ref "R29") (pin "1") (pinfunction "1_1") (pintype "passive"))
      (node (ref "R_3") (pin "A") (pinfunction "A_A") (pintype "passive"))
    )
    (net (code "75") (name "Net-(R34-Pad1)") (class "Default")
      (node (ref "R34") (pin "1") (pinfunction "1_1") (pintype "passive"))
      (node (ref "R_2") (pin "A") (pinfunction "A_A") (pintype "passive"))
    )
    (net (code "76") (name "Net-(R39-Pad1)") (class "Default")
      (node (ref "R39") (pin "1") (pinfunction "1_1") (pintype "passive"))
      (node (ref "R_1") (pin "A") (pinfunction "A_A") (pintype "passive"))
    )
    (net (code "77") (name "Net-(R44-Pad1)") (class "Default")
      (node (ref "R44") (pin "1") (pinfunction "1_1") (pintype "passive"))
      (node (ref "R_0") (pin "A") (pinfunction "A_A") (pintype "passive"))
    )
    (net (code "78") (name "Net-(T0-A1)") (class "Default")
      (node (ref "C16") (pin "2") (pinfunction "2_2") (pintype "passive"))
      (node (ref "R0-OUT") (pin "A1") (pinfunction "1_A1") (pintype "passive"))
      (node (ref "R0-OUT") (pin "A2") (pinfunction "1_A2") (pintype "passive"))
      (node (ref "R41") (pin "2") (pinfunction "2_2") (pintype "passive"))
      (node (ref "T0") (pin "T1") (pinfunction "A1_T1") (pintype "passive"))
    )
    (net (code "79") (name "Net-(T0-A2)") (class "Default")
      (node (ref "R0-IN") (pin "A1") (pinfunction "1_A1") (pintype "passive"))
      (node (ref "R0-IN") (pin "A2") (pinfunction "1_A2") (pintype "passive"))
      (node (ref "R42") (pin "2") (pinfunction "2_2") (pintype "passive"))
      (node (ref "R43") (pin "2") (pinfunction "2_2") (pintype "passive"))
      (node (ref "T0") (pin "T2") (pinfunction "A2_T2") (pintype "passive"))
    )
    (net (code "80") (name "Net-(T1-A1)") (class "Default")
      (node (ref "C15") (pin "2") (pinfunction "2_2") (pintype "passive"))
      (node (ref "R1-OUT") (pin "A1") (pinfunction "1_A1") (pintype "passive"))
      (node (ref "R1-OUT") (pin "A2") (pinfunction "1_A2") (pintype "passive"))
      (node (ref "R36") (pin "2") (pinfunction "2_2") (pintype "passive"))
      (node (ref "T1") (pin "T1") (pinfunction "A1_T1") (pintype "passive"))
    )
    (net (code "81") (name "Net-(T1-A2)") (class "Default")
      (node (ref "R1-IN") (pin "A1") (pinfunction "1_A1") (pintype "passive"))
      (node (ref "R1-IN") (pin "A2") (pinfunction "1_A2") (pintype "passive"))
      (node (ref "R37") (pin "2") (pinfunction "2_2") (pintype "passive"))
      (node (ref "R38") (pin "2") (pinfunction "2_2") (pintype "passive"))
      (node (ref "T1") (pin "T2") (pinfunction "A2_T2") (pintype "passive"))
    )
    (net (code "82") (name "Net-(T2-A1)") (class "Default")
      (node (ref "C14") (pin "2") (pinfunction "2_2") (pintype "passive"))
      (node (ref "R2-OUT") (pin "A1") (pinfunction "1_A1") (pintype "passive"))
      (node (ref "R2-OUT") (pin "A2") (pinfunction "1_A2") (pintype "passive"))
      (node (ref "R31") (pin "2") (pinfunction "2_2") (pintype "passive"))
      (node (ref "T2") (pin "T1") (pinfunction "A1_T1") (pintype "passive"))
    )
    (net (code "83") (name "Net-(T2-A2)") (class "Default")
      (node (ref "R2-IN") (pin "A1") (pinfunction "1_A1") (pintype "passive"))
      (node (ref "R2-IN") (pin "A2") (pinfunction "1_A2") (pintype "passive"))
      (node (ref "R32") (pin "2") (pinfunction "2_2") (pintype "passive"))
      (node (ref "R33") (pin "2") (pinfunction "2_2") (pintype "passive"))
      (node (ref "T2") (pin "T2") (pinfunction "A2_T2") (pintype "passive"))
    )
    (net (code "84") (name "Net-(T3-A1)") (class "Default")
      (node (ref "C13") (pin "2") (pinfunction "2_2") (pintype "passive"))
      (node (ref "R26") (pin "2") (pinfunction "2_2") (pintype "passive"))
      (node (ref "R3-OUT") (pin "A1") (pinfunction "1_A1") (pintype "passive"))
      (node (ref "R3-OUT") (pin "A2") (pinfunction "1_A2") (pintype "passive"))
      (node (ref "T3") (pin "T1") (pinfunction "A1_T1") (pintype "passive"))
    )
    (net (code "85") (name "Net-(T3-A2)") (class "Default")
      (node (ref "R27") (pin "2") (pinfunction "2_2") (pintype "passive"))
      (node (ref "R28") (pin "2") (pinfunction "2_2") (pintype "passive"))
      (node (ref "R3-IN") (pin "A1") (pinfunction "1_A1") (pintype "passive"))
      (node (ref "R3-IN") (pin "A2") (pinfunction "1_A2") (pintype "passive"))
      (node (ref "T3") (pin "T2") (pinfunction "A2_T2") (pintype "passive"))
    )
    (net (code "86") (name "Net-(T4-A1)") (class "Default")
      (node (ref "C12") (pin "2") (pinfunction "2_2") (pintype "passive"))
      (node (ref "R21") (pin "2") (pinfunction "2_2") (pintype "passive"))
      (node (ref "R4-OUT") (pin "A1") (pinfunction "1_A1") (pintype "passive"))
      (node (ref "R4-OUT") (pin "A2") (pinfunction "1_A2") (pintype "passive"))
      (node (ref "T4") (pin "T1") (pinfunction "A1_T1") (pintype "passive"))
    )
    (net (code "87") (name "Net-(T4-A2)") (class "Default")
      (node (ref "R22") (pin "2") (pinfunction "2_2") (pintype "passive"))
      (node (ref "R23") (pin "2") (pinfunction "2_2") (pintype "passive"))
      (node (ref "R4-IN") (pin "A1") (pinfunction "1_A1") (pintype "passive"))
      (node (ref "R4-IN") (pin "A2") (pinfunction "1_A2") (pintype "passive"))
      (node (ref "T4") (pin "T2") (pinfunction "A2_T2") (pintype "passive"))
    )
    (net (code "88") (name "Net-(T5-A1)") (class "Default")
      (node (ref "C11") (pin "2") (pinfunction "2_2") (pintype "passive"))
      (node (ref "R16") (pin "2") (pinfunction "2_2") (pintype "passive"))
      (node (ref "R5-OUT") (pin "A1") (pinfunction "1_A1") (pintype "passive"))
      (node (ref "R5-OUT") (pin "A2") (pinfunction "1_A2") (pintype "passive"))
      (node (ref "T5") (pin "T1") (pinfunction "A1_T1") (pintype "passive"))
    )
    (net (code "89") (name "Net-(T5-A2)") (class "Default")
      (node (ref "R17") (pin "2") (pinfunction "2_2") (pintype "passive"))
      (node (ref "R18") (pin "2") (pinfunction "2_2") (pintype "passive"))
      (node (ref "R5-IN") (pin "A1") (pinfunction "1_A1") (pintype "passive"))
      (node (ref "R5-IN") (pin "A2") (pinfunction "1_A2") (pintype "passive"))
      (node (ref "T5") (pin "T2") (pinfunction "A2_T2") (pintype "passive"))
    )
    (net (code "90") (name "Net-(T6-A1)") (class "Default")
      (node (ref "C10") (pin "2") (pinfunction "2_2") (pintype "passive"))
      (node (ref "R11") (pin "2") (pinfunction "2_2") (pintype "passive"))
      (node (ref "R6-OUT") (pin "A1") (pinfunction "1_A1") (pintype "passive"))
      (node (ref "R6-OUT") (pin "A2") (pinfunction "1_A2") (pintype "passive"))
      (node (ref "T6") (pin "T1") (pinfunction "A1_T1") (pintype "passive"))
    )
    (net (code "91") (name "Net-(T6-A2)") (class "Default")
      (node (ref "R12") (pin "2") (pinfunction "2_2") (pintype "passive"))
      (node (ref "R13") (pin "2") (pinfunction "2_2") (pintype "passive"))
      (node (ref "R6-IN") (pin "A1") (pinfunction "1_A1") (pintype "passive"))
      (node (ref "R6-IN") (pin "A2") (pinfunction "1_A2") (pintype "passive"))
      (node (ref "T6") (pin "T2") (pinfunction "A2_T2") (pintype "passive"))
    )
    (net (code "92") (name "Net-(T7-A1)") (class "Default")
      (node (ref "C9") (pin "2") (pinfunction "2_2") (pintype "passive"))
      (node (ref "R6") (pin "2") (pinfunction "2_2") (pintype "passive"))
      (node (ref "R7-OUT") (pin "A1") (pinfunction "1_A1") (pintype "passive"))
      (node (ref "R7-OUT") (pin "A2") (pinfunction "1_A2") (pintype "passive"))
      (node (ref "T7") (pin "T1") (pinfunction "A1_T1") (pintype "passive"))
    )
    (net (code "93") (name "Net-(T7-A2)") (class "Default")
      (node (ref "R7") (pin "2") (pinfunction "2_2") (pintype "passive"))
      (node (ref "R7-IN") (pin "A1") (pinfunction "1_A1") (pintype "passive"))
      (node (ref "R7-IN") (pin "A2") (pinfunction "1_A2") (pintype "passive"))
      (node (ref "R8") (pin "2") (pinfunction "2_2") (pintype "passive"))
      (node (ref "T7") (pin "T2") (pinfunction "A2_T2") (pintype "passive"))
    )
    (net (code "94") (name "Net-(U1-PA00(XIN32{slash}SER1:0{slash}TC2:0))") (class "Default")
      (node (ref "C2") (pin "2") (pinfunction "2_2") (pintype "passive"))
      (node (ref "U1") (pin "1") (pinfunction "PA00(XIN32/SER1:0/TC2:0)_1") (pintype "bidirectional"))
      (node (ref "Y1") (pin "P$2") (pinfunction "2_P$2") (pintype "passive"))
    )
    (net (code "95") (name "Net-(U1-PA01(XOUT32{slash}SER1:1{slash}TC2:1))") (class "Default")
      (node (ref "C1") (pin "2") (pinfunction "2_2") (pintype "passive"))
      (node (ref "U1") (pin "2") (pinfunction "PA01(XOUT32/SER1:1/TC2:1)_2") (pintype "bidirectional"))
      (node (ref "Y1") (pin "P$1") (pinfunction "1_P$1") (pintype "passive"))
    )
    (net (code "96") (name "Net-(U1-VDDANA)") (class "Default")
      (node (ref "C3") (pin "2") (pinfunction "2_2") (pintype "passive"))
      (node (ref "FB1") (pin "1") (pinfunction "1_1") (pintype "passive"))
      (node (ref "U1") (pin "6") (pinfunction "VDDANA_6") (pintype "bidirectional"))
    )
    (net (code "97") (name "Net-(U1-VDDCORE)") (class "Default")
      (node (ref "C4") (pin "2") (pinfunction "2_2") (pintype "passive"))
      (node (ref "U1") (pin "43") (pinfunction "VDDCORE_43") (pintype "bidirectional"))
    )
    (net (code "98") (name "RCTL0_HV") (class "Default")
      (node (ref "OPT0") (pin "2") (pinfunction "C_2") (pintype "passive"))
      (node (ref "Q8") (pin "3") (pinfunction "D_3") (pintype "bidirectional"))
      (node (ref "R_0") (pin "C") (pinfunction "C_C") (pintype "passive"))
    )
    (net (code "99") (name "RCTL0_LV") (class "Default")
      (node (ref "R59") (pin "1") (pinfunction "1_1") (pintype "passive"))
      (node (ref "U1") (pin "3") (pinfunction "PA02(AIN0/DAC)_3") (pintype "bidirectional"))
    )
    (net (code "100") (name "RCTL1_HV") (class "Default")
      (node (ref "OPT1") (pin "2") (pinfunction "C_2") (pintype "passive"))
      (node (ref "Q7") (pin "3") (pinfunction "D_3") (pintype "bidirectional"))
      (node (ref "R_1") (pin "C") (pinfunction "C_C") (pintype "passive"))
    )
    (net (code "101") (name "RCTL1_LV") (class "Default")
      (node (ref "R57") (pin "1") (pinfunction "1_1") (pintype "passive"))
      (node (ref "U1") (pin "4") (pinfunction "PA03(AIN1/REFA)_4") (pintype "bidirectional"))
    )
    (net (code "102") (name "RCTL2_HV") (class "Default")
      (node (ref "OPT2") (pin "2") (pinfunction "C_2") (pintype "passive"))
      (node (ref "Q6") (pin "3") (pinfunction "D_3") (pintype "bidirectional"))
      (node (ref "R_2") (pin "C") (pinfunction "C_C") (pintype "passive"))
    )
    (net (code "103") (name "RCTL2_LV") (class "Default")
      (node (ref "R55") (pin "1") (pinfunction "1_1") (pintype "passive"))
      (node (ref "U1") (pin "9") (pinfunction "PA04(AIN4/REFB/SER0:0/TC0:0)_9") (pintype "bidirectional"))
    )
    (net (code "104") (name "RCTL3_HV") (class "Default")
      (node (ref "OPT3") (pin "2") (pinfunction "C_2") (pintype "passive"))
      (node (ref "Q5") (pin "3") (pinfunction "D_3") (pintype "bidirectional"))
      (node (ref "R_3") (pin "C") (pinfunction "C_C") (pintype "passive"))
    )
    (net (code "105") (name "RCTL3_LV") (class "Default")
      (node (ref "R53") (pin "1") (pinfunction "1_1") (pintype "passive"))
      (node (ref "U1") (pin "10") (pinfunction "PA05(AIN5/SER0:1/TC0:1)_10") (pintype "bidirectional"))
    )
    (net (code "106") (name "RCTL4_HV") (class "Default")
      (node (ref "OPT4") (pin "2") (pinfunction "C_2") (pintype "passive"))
      (node (ref "Q4") (pin "3") (pinfunction "D_3") (pintype "bidirectional"))
      (node (ref "R_4") (pin "C") (pinfunction "C_C") (pintype "passive"))
    )
    (net (code "107") (name "RCTL4_LV") (class "Default")
      (node (ref "R51") (pin "1") (pinfunction "1_1") (pintype "passive"))
      (node (ref "U1") (pin "11") (pinfunction "PA06(AIN6/SER0:2/TC1:0)_11") (pintype "bidirectional"))
    )
    (net (code "108") (name "RCTL5_HV") (class "Default")
      (node (ref "OPT5") (pin "2") (pinfunction "C_2") (pintype "passive"))
      (node (ref "Q3") (pin "3") (pinfunction "D_3") (pintype "bidirectional"))
      (node (ref "R_5") (pin "C") (pinfunction "C_C") (pintype "passive"))
    )
    (net (code "109") (name "RCTL5_LV") (class "Default")
      (node (ref "R49") (pin "1") (pinfunction "1_1") (pintype "passive"))
      (node (ref "U1") (pin "12") (pinfunction "PA07(AIN7/SER0:3/TC1:1)_12") (pintype "bidirectional"))
    )
    (net (code "110") (name "RCTL6_HV") (class "Default")
      (node (ref "OPT6") (pin "2") (pinfunction "C_2") (pintype "passive"))
      (node (ref "Q2") (pin "3") (pinfunction "D_3") (pintype "bidirectional"))
      (node (ref "R_6") (pin "C") (pinfunction "C_C") (pintype "passive"))
    )
    (net (code "111") (name "RCTL6_LV") (class "Default")
      (node (ref "R47") (pin "1") (pinfunction "1_1") (pintype "passive"))
      (node (ref "U1") (pin "13") (pinfunction "PA08(I2C/AIN16/SER0:0+)_13") (pintype "bidirectional"))
    )
    (net (code "112") (name "RCTL7_HV") (class "Default")
      (node (ref "OPT7") (pin "2") (pinfunction "C_2") (pintype "passive"))
      (node (ref "Q1") (pin "3") (pinfunction "D_3") (pintype "bidirectional"))
      (node (ref "R_7") (pin "C") (pinfunction "C_C") (pintype "passive"))
    )
    (net (code "113") (name "RCTL7_LV") (class "Default")
      (node (ref "R45") (pin "1") (pinfunction "1_1") (pintype "passive"))
      (node (ref "U1") (pin "14") (pinfunction "PA09(I2C/AIN17/SER0:1+)_14") (pintype "bidirectional"))
    )
    (net (code "114") (name "SCL") (class "Default")
      (node (ref "R61") (pin "1") (pinfunction "1_1") (pintype "passive"))
      (node (ref "U1") (pin "32") (pinfunction "PA23(I2C/SER3:0+)_32") (pintype "bidirectional"))
      (node (ref "U3") (pin "6") (pinfunction "SCL_6") (pintype "bidirectional"))
    )
    (net (code "115") (name "SDA") (class "Default")
      (node (ref "R62") (pin "1") (pinfunction "1_1") (pintype "passive"))
      (node (ref "U1") (pin "31") (pinfunction "PA22(I2C/SER3:0+)_31") (pintype "bidirectional"))
      (node (ref "U3") (pin "5") (pinfunction "SDA_5") (pintype "bidirectional"))
    )
    (net (code "116") (name "SWDCLK") (class "Default")
      (node (ref "J2") (pin "4") (pinfunction "SWDCLK/TCK_4") (pintype "bidirectional"))
      (node (ref "U1") (pin "45") (pinfunction "PA30(SWCLK/SER1:2+)_45") (pintype "bidirectional"))
    )
    (net (code "117") (name "SWDIO") (class "Default")
      (node (ref "J2") (pin "2") (pinfunction "SWDIO/TMS_2") (pintype "bidirectional"))
      (node (ref "U1") (pin "46") (pinfunction "PA31(SWDIO/SER1:3+)_46") (pintype "bidirectional"))
    )
    (net (code "118") (name "USB_D+") (class "Default")
      (node (ref "J1") (pin "D+") (pinfunction "D+_D+") (pintype "bidirectional"))
      (node (ref "U1") (pin "34") (pinfunction "PA25(SER3:3+)_34") (pintype "bidirectional"))
    )
    (net (code "119") (name "USB_D-") (class "Default")
      (node (ref "J1") (pin "D-") (pinfunction "D-_D-") (pintype "bidirectional"))
      (node (ref "U1") (pin "33") (pinfunction "PA24(SER3:2+)_33") (pintype "bidirectional"))
    )
    (net (code "120") (name "USB_SENSE") (class "Default")
      (node (ref "R2") (pin "1") (pinfunction "1_1") (pintype "passive"))
      (node (ref "R3") (pin "2") (pinfunction "2_2") (pintype "passive"))
      (node (ref "U1") (pin "41") (pinfunction "PA28_41") (pintype "bidirectional"))
    )
    (net (code "121") (name "unconnected-(H1-Pad1)") (class "Default")
      (node (ref "H1") (pin "1") (pinfunction "1_1") (pintype "passive"))
    )
    (net (code "122") (name "unconnected-(H2-Pad1)") (class "Default")
      (node (ref "H2") (pin "1") (pinfunction "1_1") (pintype "passive"))
    )
    (net (code "123") (name "unconnected-(H3-Pad1)") (class "Default")
      (node (ref "H3") (pin "1") (pinfunction "1_1") (pintype "passive"))
    )
    (net (code "124") (name "unconnected-(H4-Pad1)") (class "Default")
      (node (ref "H4") (pin "1") (pinfunction "1_1") (pintype "passive"))
    )
    (net (code "125") (name "unconnected-(H5-Pad1)") (class "Default")
      (node (ref "H5") (pin "1") (pinfunction "1_1") (pintype "passive"))
    )
    (net (code "126") (name "unconnected-(J1-PadID)") (class "Default")
      (node (ref "J1") (pin "ID") (pinfunction "ID_ID") (pintype "bidirectional"))
    )
    (net (code "127") (name "unconnected-(J2-KEY-Pad7)") (class "Default")
      (node (ref "J2") (pin "7") (pinfunction "KEY_7") (pintype "bidirectional"))
    )
    (net (code "128") (name "unconnected-(J2-NC{slash}TDI-Pad8)") (class "Default")
      (node (ref "J2") (pin "8") (pinfunction "NC/TDI_8") (pintype "bidirectional"))
    )
    (net (code "129") (name "unconnected-(J2-SWO{slash}TDO-Pad6)") (class "Default")
      (node (ref "J2") (pin "6") (pinfunction "SWO/TDO_6") (pintype "bidirectional"))
    )
    (net (code "130") (name "unconnected-(U2-NC-Pad4)") (class "Default")
      (node (ref "U2") (pin "4") (pinfunction "NC_4") (pintype "no_connect"))
    )
    (net (code "131") (name "~{RESET}") (class "Default")
      (node (ref "J2") (pin "10") (pinfunction "~{RESET}_10") (pintype "bidirectional"))
      (node (ref "R1") (pin "1") (pinfunction "1_1") (pintype "passive"))
      (node (ref "S1") (pin "1") (pinfunction "1_1") (pintype "passive"))
      (node (ref "U1") (pin "40") (pinfunction "~{RESET}_40") (pintype "bidirectional"))
    )
  )
)
